# pm25.net
KiCad netlist of a schematic drawn in EAGLE
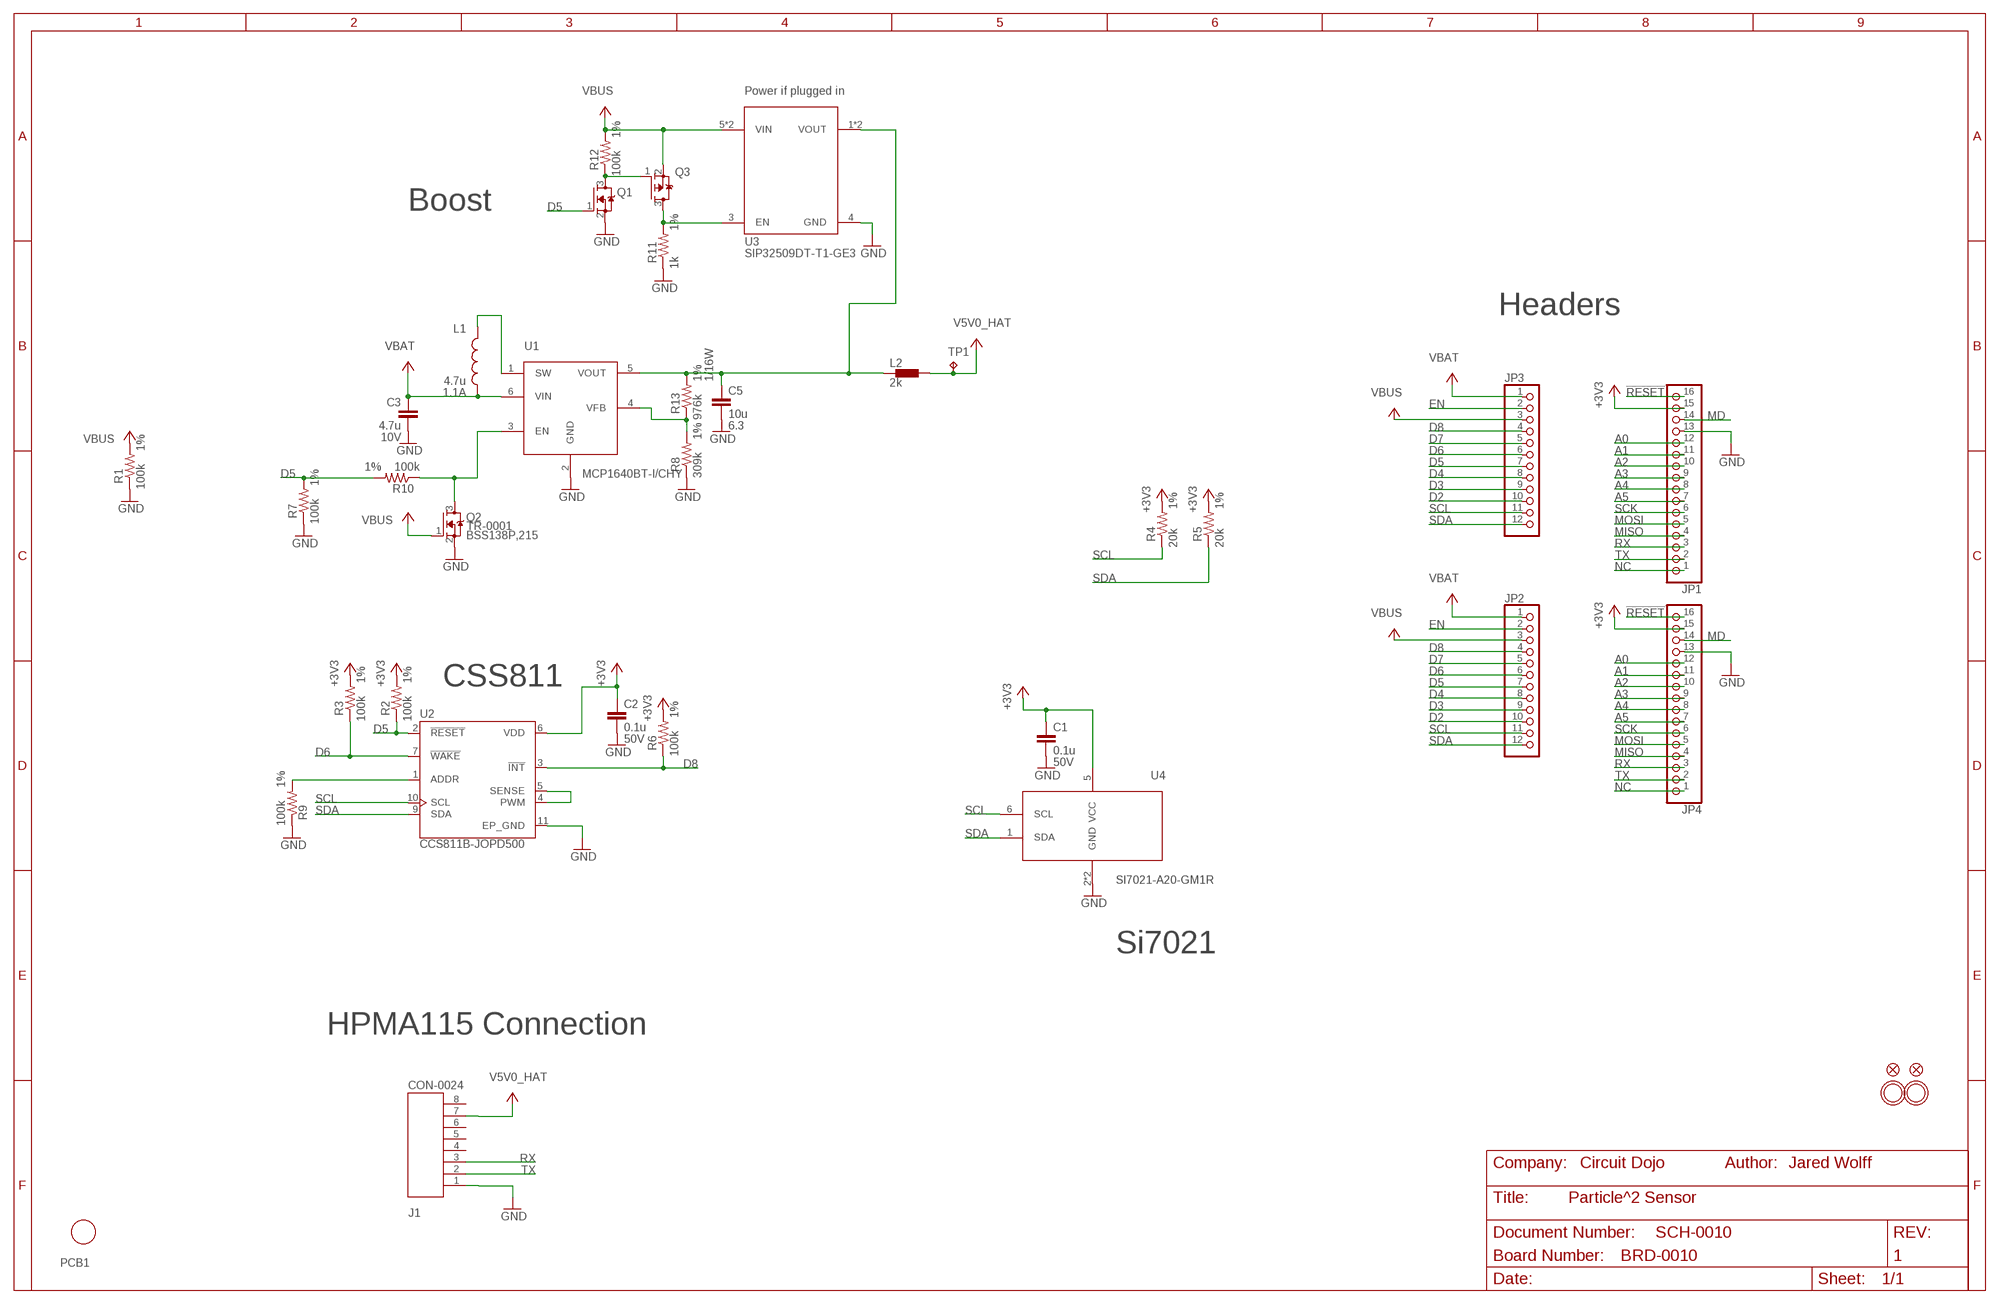
[diagram p0: schematic, sheet 1]

(export (version "E")
  (design (tool "Eeschema 10.0.6"))
  (components
    (comp (ref "C1")
      (value "0.1u")
      (footprint "eagle-import:CAPC1005X55N")
      (fields
        (field (name "VOLTHIGH") "50V")
        (field (name "MF") "Taiyo Yuden")
        (field (name "MPN") "UMK105BJ104KV-F")
      )
      (libsource (lib "eagle-import") (part "CAP-0017"))
    )
    (comp (ref "C2")
      (value "0.1u")
      (footprint "eagle-import:CAPC1005X55N")
      (fields
        (field (name "VOLTHIGH") "50V")
        (field (name "MF") "Taiyo Yuden")
        (field (name "MPN") "UMK105BJ104KV-F")
      )
      (libsource (lib "eagle-import") (part "CAP-0017"))
    )
    (comp (ref "C3")
      (value "4.7u")
      (footprint "eagle-import:C0603")
      (fields (field (name "VOLTHIGH") "10V") (field (name "MPN") "CL10A475MP5LNNC"))
      (libsource (lib "eagle-import") (part "CAP-0010"))
    )
    (comp (ref "C5")
      (value "10u")
      (footprint "eagle-import:C0603")
      (fields (field (name "MPN") "JMK107ABJ106MA-T") (field (name "VOLTHIGH") "6.3"))
      (libsource (lib "eagle-import") (part "CAP-0603-10U-6.3V"))
    )
    (comp (ref "J1")
      (value "CON-0024")
      (footprint "eagle-import:0532610871")
      (fields (field (name "MPN") "0532610871"))
      (libsource (lib "eagle-import") (part "CON-0024"))
    )
    (comp (ref "JP1")
      (value "HEADER-1X16ROUND")
      (footprint "eagle-import:1X16_ROUND")
      (fields (field (name "MPN") "PPPC161LFBN-RC"))
      (libsource (lib "eagle-import") (part "HEADER-1X16ROUND"))
    )
    (comp (ref "JP2")
      (value "HEADER-1X12")
      (footprint "eagle-import:1X12_ROUND")
      (libsource (lib "eagle-import") (part "HEADER-1X12"))
    )
    (comp (ref "JP3")
      (value "HEADER-1X12")
      (footprint "eagle-import:1X12_ROUND")
      (fields (field (name "MPN") "PPPC121LFBN-RC"))
      (libsource (lib "eagle-import") (part "HEADER-1X12"))
    )
    (comp (ref "JP4")
      (value "HEADER-1X16ROUND")
      (footprint "eagle-import:1X16_ROUND")
      (libsource (lib "eagle-import") (part "HEADER-1X16ROUND"))
    )
    (comp (ref "L1")
      (value "4.7u")
      (footprint "eagle-import:IND-2P0X2P0X1P2")
      (fields (field (name "CURRENT") "1.1A") (field (name "MPN") "NRV2012T4R7MGF"))
      (libsource (lib "eagle-import") (part "IND-0003"))
    )
    (comp (ref "L2")
      (value "2k")
      (footprint "eagle-import:R0805")
      (fields (field (name "MPN") "CIM21J202NE"))
      (libsource (lib "eagle-import") (part "FERRITE-0805"))
    )
    (comp (ref "PCB1")
      (value "PCB-PS-CCS811-SI7021")
      (footprint "eagle-import:PLACEHOLDER")
      (fields (field (name "MPN") "BRD-0010"))
      (libsource (lib "eagle-import") (part "PCB-PS-CCS811-SI7021"))
    )
    (comp (ref "Q1")
      (value "TR-0001")
      (footprint "eagle-import:SOT23")
      (fields (field (name "MPN") "BSS138P,215"))
      (libsource (lib "eagle-import") (part "TR-0001"))
    )
    (comp (ref "Q2")
      (value "TR-0001")
      (footprint "eagle-import:SOT23")
      (fields (field (name "MPN") "BSS138P,215"))
      (libsource (lib "eagle-import") (part "TR-0001"))
    )
    (comp (ref "Q3")
      (value "TR-0003")
      (footprint "eagle-import:SOT23")
      (fields (field (name "MPN") "BSS84-7-F"))
      (libsource (lib "eagle-import") (part "TR-0003"))
    )
    (comp (ref "R1")
      (value "100k")
      (footprint "eagle-import:R0402")
      (fields (field (name "TOLERANCE") "1%") (field (name "MPN") "RC0402FR07100KL"))
      (libsource (lib "eagle-import") (part "RES-0041"))
    )
    (comp (ref "R2")
      (value "100k")
      (footprint "eagle-import:R0402")
      (fields (field (name "TOLERANCE") "1%") (field (name "MPN") "RC0402FR07100KL"))
      (libsource (lib "eagle-import") (part "RES-0041"))
    )
    (comp (ref "R3")
      (value "100k")
      (footprint "eagle-import:R0402")
      (fields (field (name "TOLERANCE") "1%") (field (name "MPN") "RC0402FR07100KL"))
      (libsource (lib "eagle-import") (part "RES-0041"))
    )
    (comp (ref "R4")
      (value "20k")
      (footprint "eagle-import:R0402")
      (fields (field (name "TOLERANCE") "1%") (field (name "MPN") "RC0402FR-0720KL"))
      (libsource (lib "eagle-import") (part "RES-0054"))
    )
    (comp (ref "R5")
      (value "20k")
      (footprint "eagle-import:R0402")
      (fields (field (name "TOLERANCE") "1%") (field (name "MPN") "RC0402FR-0720KL"))
      (libsource (lib "eagle-import") (part "RES-0054"))
    )
    (comp (ref "R6")
      (value "100k")
      (footprint "eagle-import:R0402")
      (fields (field (name "TOLERANCE") "1%") (field (name "MPN") "RC0402FR07100KL"))
      (libsource (lib "eagle-import") (part "RES-0041"))
    )
    (comp (ref "R7")
      (value "100k")
      (footprint "eagle-import:R0402")
      (fields (field (name "TOLERANCE") "1%") (field (name "MPN") "RC0402FR07100KL"))
      (libsource (lib "eagle-import") (part "RES-0041"))
    )
    (comp (ref "R8")
      (value "309k")
      (footprint "eagle-import:R0402")
      (fields
        (field (name "MPN") "RC0402FR-07309KL")
        (field (name "POWER") "1/16W")
        (field (name "TOLERANCE") "1%")
      )
      (libsource (lib "eagle-import") (part "RES-0402-309K-1%"))
    )
    (comp (ref "R9")
      (value "100k")
      (footprint "eagle-import:R0402")
      (fields (field (name "TOLERANCE") "1%") (field (name "MPN") "RC0402FR07100KL"))
      (libsource (lib "eagle-import") (part "RES-0041"))
    )
    (comp (ref "R10")
      (value "100k")
      (footprint "eagle-import:R0402")
      (fields (field (name "TOLERANCE") "1%") (field (name "MPN") "RC0402FR07100KL"))
      (libsource (lib "eagle-import") (part "RES-0041"))
    )
    (comp (ref "R11")
      (value "1k")
      (footprint "eagle-import:R0402")
      (fields
        (field (name "MPN") "RCS04021K00FKED")
        (field (name "POWER") "1/5W")
        (field (name "TOLERANCE") "1%")
      )
      (libsource (lib "eagle-import") (part "RES-0402-1K-1%"))
    )
    (comp (ref "R12")
      (value "100k")
      (footprint "eagle-import:R0402")
      (fields (field (name "TOLERANCE") "1%") (field (name "MPN") "RC0402FR07100KL"))
      (libsource (lib "eagle-import") (part "RES-0041"))
    )
    (comp (ref "R13")
      (value "976k")
      (footprint "eagle-import:R0402")
      (fields
        (field (name "MPN") "RC0402FR-07976KL")
        (field (name "POWER") "1/16W")
        (field (name "TOLERANCE") "1%")
      )
      (libsource (lib "eagle-import") (part "RES-0402-976K-1%"))
    )
    (comp (ref "TP1")
      (value "TP")
      (footprint "eagle-import:TP-1P27")
      (libsource (lib "eagle-import") (part "TP"))
    )
    (comp (ref "U$31")
      (value "MOUNTINGHOLE2.5")
      (footprint "eagle-import:MOUNTINGHOLE_2.5_PLATED")
      (libsource (lib "eagle-import") (part "MOUNTINGHOLE2.5"))
    )
    (comp (ref "U$32")
      (value "MOUNTINGHOLE2.5")
      (footprint "eagle-import:MOUNTINGHOLE_2.5_PLATED")
      (libsource (lib "eagle-import") (part "MOUNTINGHOLE2.5"))
    )
    (comp (ref "U$34")
      (value "FIDUCIAL\"\"")
      (footprint "eagle-import:FIDUCIAL_1MM")
      (libsource (lib "eagle-import") (part "FIDUCIAL{dblquote}{dblquote}"))
    )
    (comp (ref "U$35")
      (value "FIDUCIAL\"\"")
      (footprint "eagle-import:FIDUCIAL_1MM")
      (libsource (lib "eagle-import") (part "FIDUCIAL{dblquote}{dblquote}"))
    )
    (comp (ref "U1")
      (value "POWER-VREG-FB-EN-SW-350MA")
      (footprint "eagle-import:SOT23-6")
      (fields (field (name "MPN") "MCP1640BT-I/CHY"))
      (libsource (lib "eagle-import") (part "POWER-VREG-FB-EN-SW-350MA"))
    )
    (comp (ref "U2")
      (value "CCS811B-JOPD500")
      (footprint "eagle-import:SON60P400X270X110-11N")
      (fields (field (name "MF") "ams"))
      (libsource (lib "eagle-import") (part "CCS811B-JOPD500"))
    )
    (comp (ref "U3")
      (value "POWER-SWITCH-SIP32509DT")
      (footprint "eagle-import:SOT23-6")
      (fields (field (name "MPN") "SIP32509DT-T1-GE3"))
      (libsource (lib "eagle-import") (part "POWER-SWITCH-SIP32509DT"))
    )
    (comp (ref "U4")
      (value "SI7021-A20-GM1R")
      (footprint "eagle-import:SON100P300X300X80-7N")
      (fields (field (name "MPN") "SI7021-A20-GM1R"))
      (libsource (lib "eagle-import") (part "SI7021-A20-GM1R"))
    )
  )
  (nets
    (net (code "1") (name "+3V3") (class "Default")
      (node (ref "C1") (pin "1") (pinfunction "1_1") (pintype "passive"))
      (node (ref "C2") (pin "1") (pinfunction "1_1") (pintype "passive"))
      (node (ref "JP1") (pin "15") (pinfunction "15_15") (pintype "passive"))
      (node (ref "JP4") (pin "15") (pinfunction "15_15") (pintype "passive"))
      (node (ref "R2") (pin "2") (pinfunction "2_2") (pintype "passive"))
      (node (ref "R3") (pin "2") (pinfunction "2_2") (pintype "passive"))
      (node (ref "R4") (pin "2") (pinfunction "2_2") (pintype "passive"))
      (node (ref "R5") (pin "2") (pinfunction "2_2") (pintype "passive"))
      (node (ref "R6") (pin "2") (pinfunction "2_2") (pintype "passive"))
      (node (ref "U2") (pin "6") (pinfunction "VDD_6") (pintype "power_in"))
      (node (ref "U4") (pin "5") (pinfunction "VCC_5") (pintype "bidirectional"))
    )
    (net (code "2") (name "/A0") (class "Default")
      (node (ref "JP1") (pin "12") (pinfunction "12_12") (pintype "passive"))
      (node (ref "JP4") (pin "12") (pinfunction "12_12") (pintype "passive"))
    )
    (net (code "3") (name "/A1") (class "Default")
      (node (ref "JP1") (pin "11") (pinfunction "11_11") (pintype "passive"))
      (node (ref "JP4") (pin "11") (pinfunction "11_11") (pintype "passive"))
    )
    (net (code "4") (name "/A2") (class "Default")
      (node (ref "JP1") (pin "10") (pinfunction "10_10") (pintype "passive"))
      (node (ref "JP4") (pin "10") (pinfunction "10_10") (pintype "passive"))
    )
    (net (code "5") (name "/A3") (class "Default")
      (node (ref "JP1") (pin "9") (pinfunction "9_9") (pintype "passive"))
      (node (ref "JP4") (pin "9") (pinfunction "9_9") (pintype "passive"))
    )
    (net (code "6") (name "/A4") (class "Default")
      (node (ref "JP1") (pin "8") (pinfunction "8_8") (pintype "passive"))
      (node (ref "JP4") (pin "8") (pinfunction "8_8") (pintype "passive"))
    )
    (net (code "7") (name "/A5") (class "Default")
      (node (ref "JP1") (pin "7") (pinfunction "7_7") (pintype "passive"))
      (node (ref "JP4") (pin "7") (pinfunction "7_7") (pintype "passive"))
    )
    (net (code "8") (name "/D2") (class "Default")
      (node (ref "JP2") (pin "10") (pinfunction "10_10") (pintype "passive"))
      (node (ref "JP3") (pin "10") (pinfunction "10_10") (pintype "passive"))
    )
    (net (code "9") (name "/D3") (class "Default")
      (node (ref "JP2") (pin "9") (pinfunction "9_9") (pintype "passive"))
      (node (ref "JP3") (pin "9") (pinfunction "9_9") (pintype "passive"))
    )
    (net (code "10") (name "/D4") (class "Default")
      (node (ref "JP2") (pin "8") (pinfunction "8_8") (pintype "passive"))
      (node (ref "JP3") (pin "8") (pinfunction "8_8") (pintype "passive"))
    )
    (net (code "11") (name "/D5") (class "Default")
      (node (ref "JP2") (pin "7") (pinfunction "7_7") (pintype "passive"))
      (node (ref "JP3") (pin "7") (pinfunction "7_7") (pintype "passive"))
      (node (ref "Q1") (pin "1") (pinfunction "G_1") (pintype "bidirectional"))
      (node (ref "R10") (pin "2") (pinfunction "2_2") (pintype "passive"))
      (node (ref "R2") (pin "1") (pinfunction "1_1") (pintype "passive"))
      (node (ref "R7") (pin "2") (pinfunction "2_2") (pintype "passive"))
      (node (ref "U2") (pin "2") (pinfunction "~{RESET}_2") (pintype "input"))
    )
    (net (code "12") (name "/D6") (class "Default")
      (node (ref "JP2") (pin "6") (pinfunction "6_6") (pintype "passive"))
      (node (ref "JP3") (pin "6") (pinfunction "6_6") (pintype "passive"))
      (node (ref "R3") (pin "1") (pinfunction "1_1") (pintype "passive"))
      (node (ref "U2") (pin "7") (pinfunction "~{WAKE}_7") (pintype "input"))
    )
    (net (code "13") (name "/D7") (class "Default")
      (node (ref "JP2") (pin "5") (pinfunction "5_5") (pintype "passive"))
      (node (ref "JP3") (pin "5") (pinfunction "5_5") (pintype "passive"))
    )
    (net (code "14") (name "/D8") (class "Default")
      (node (ref "JP2") (pin "4") (pinfunction "4_4") (pintype "passive"))
      (node (ref "JP3") (pin "4") (pinfunction "4_4") (pintype "passive"))
      (node (ref "R6") (pin "1") (pinfunction "1_1") (pintype "passive"))
      (node (ref "U2") (pin "3") (pinfunction "~{INT}_3") (pintype "output"))
    )
    (net (code "15") (name "/EN") (class "Default")
      (node (ref "JP2") (pin "2") (pinfunction "2_2") (pintype "passive"))
      (node (ref "JP3") (pin "2") (pinfunction "2_2") (pintype "passive"))
    )
    (net (code "16") (name "/MD") (class "Default")
      (node (ref "JP1") (pin "14") (pinfunction "14_14") (pintype "passive"))
      (node (ref "JP4") (pin "14") (pinfunction "14_14") (pintype "passive"))
    )
    (net (code "17") (name "/MISO") (class "Default")
      (node (ref "JP1") (pin "4") (pinfunction "4_4") (pintype "passive"))
      (node (ref "JP4") (pin "4") (pinfunction "4_4") (pintype "passive"))
    )
    (net (code "18") (name "/MOSI") (class "Default")
      (node (ref "JP1") (pin "5") (pinfunction "5_5") (pintype "passive"))
      (node (ref "JP4") (pin "5") (pinfunction "5_5") (pintype "passive"))
    )
    (net (code "19") (name "/NC") (class "Default")
      (node (ref "JP1") (pin "1") (pinfunction "1_1") (pintype "passive"))
      (node (ref "JP4") (pin "1") (pinfunction "1_1") (pintype "passive"))
    )
    (net (code "20") (name "/RX") (class "Default")
      (node (ref "J1") (pin "3") (pinfunction "P$3_3") (pintype "bidirectional"))
      (node (ref "JP1") (pin "3") (pinfunction "3_3") (pintype "passive"))
      (node (ref "JP4") (pin "3") (pinfunction "3_3") (pintype "passive"))
    )
    (net (code "21") (name "/SCK") (class "Default")
      (node (ref "JP1") (pin "6") (pinfunction "6_6") (pintype "passive"))
      (node (ref "JP4") (pin "6") (pinfunction "6_6") (pintype "passive"))
    )
    (net (code "22") (name "/SCL") (class "Default")
      (node (ref "JP2") (pin "11") (pinfunction "11_11") (pintype "passive"))
      (node (ref "JP3") (pin "11") (pinfunction "11_11") (pintype "passive"))
      (node (ref "R4") (pin "1") (pinfunction "1_1") (pintype "passive"))
      (node (ref "U2") (pin "10") (pinfunction "SCL_10") (pintype "input"))
      (node (ref "U4") (pin "6") (pinfunction "SCL_6") (pintype "bidirectional"))
    )
    (net (code "23") (name "/SDA") (class "Default")
      (node (ref "JP2") (pin "12") (pinfunction "12_12") (pintype "passive"))
      (node (ref "JP3") (pin "12") (pinfunction "12_12") (pintype "passive"))
      (node (ref "R5") (pin "1") (pinfunction "1_1") (pintype "passive"))
      (node (ref "U2") (pin "9") (pinfunction "SDA_9") (pintype "bidirectional"))
      (node (ref "U4") (pin "1") (pinfunction "SDA_1") (pintype "bidirectional"))
    )
    (net (code "24") (name "/TX") (class "Default")
      (node (ref "J1") (pin "2") (pinfunction "P$2_2") (pintype "bidirectional"))
      (node (ref "JP1") (pin "2") (pinfunction "2_2") (pintype "passive"))
      (node (ref "JP4") (pin "2") (pinfunction "2_2") (pintype "passive"))
    )
    (net (code "25") (name "/~{RESET}") (class "Default")
      (node (ref "JP1") (pin "16") (pinfunction "16_16") (pintype "passive"))
      (node (ref "JP4") (pin "16") (pinfunction "16_16") (pintype "passive"))
    )
    (net (code "26") (name "GND") (class "Default")
      (node (ref "C1") (pin "2") (pinfunction "2_2") (pintype "passive"))
      (node (ref "C2") (pin "2") (pinfunction "2_2") (pintype "passive"))
      (node (ref "C3") (pin "2") (pinfunction "2_2") (pintype "passive"))
      (node (ref "C5") (pin "2") (pinfunction "2_2") (pintype "passive"))
      (node (ref "J1") (pin "1") (pinfunction "P$1_1") (pintype "bidirectional"))
      (node (ref "JP1") (pin "13") (pinfunction "13_13") (pintype "passive"))
      (node (ref "JP4") (pin "13") (pinfunction "13_13") (pintype "passive"))
      (node (ref "Q1") (pin "2") (pinfunction "S_2") (pintype "bidirectional"))
      (node (ref "Q2") (pin "2") (pinfunction "S_2") (pintype "bidirectional"))
      (node (ref "R1") (pin "1") (pinfunction "1_1") (pintype "passive"))
      (node (ref "R11") (pin "1") (pinfunction "1_1") (pintype "passive"))
      (node (ref "R7") (pin "1") (pinfunction "1_1") (pintype "passive"))
      (node (ref "R8") (pin "1") (pinfunction "1_1") (pintype "passive"))
      (node (ref "R9") (pin "1") (pinfunction "1_1") (pintype "passive"))
      (node (ref "U1") (pin "2") (pinfunction "GND_2") (pintype "bidirectional"))
      (node (ref "U2") (pin "11") (pinfunction "EP_GND_11") (pintype "power_in"))
      (node (ref "U3") (pin "4") (pinfunction "GND_4") (pintype "power_in"))
      (node (ref "U4") (pin "2") (pinfunction "GND_2") (pintype "bidirectional"))
      (node (ref "U4") (pin "7") (pinfunction "GND_7") (pintype "bidirectional"))
    )
    (net (code "27") (name "Net-(L1-1)") (class "Default")
      (node (ref "L1") (pin "P$1") (pinfunction "1_P$1") (pintype "passive"))
      (node (ref "U1") (pin "1") (pinfunction "SW_1") (pintype "bidirectional"))
    )
    (net (code "28") (name "Net-(Q1-D)") (class "Default")
      (node (ref "Q1") (pin "3") (pinfunction "D_3") (pintype "bidirectional"))
      (node (ref "Q3") (pin "1") (pinfunction "G_1") (pintype "passive"))
      (node (ref "R12") (pin "1") (pinfunction "1_1") (pintype "passive"))
    )
    (net (code "29") (name "Net-(Q2-D)") (class "Default")
      (node (ref "Q2") (pin "3") (pinfunction "D_3") (pintype "bidirectional"))
      (node (ref "R10") (pin "1") (pinfunction "1_1") (pintype "passive"))
      (node (ref "U1") (pin "3") (pinfunction "EN_3") (pintype "bidirectional"))
    )
    (net (code "30") (name "Net-(Q3-D)") (class "Default")
      (node (ref "Q3") (pin "3") (pinfunction "D_3") (pintype "passive"))
      (node (ref "R11") (pin "2") (pinfunction "2_2") (pintype "passive"))
      (node (ref "U3") (pin "3") (pinfunction "EN_3") (pintype "input"))
    )
    (net (code "31") (name "Net-(U1-VFB)") (class "Default")
      (node (ref "R13") (pin "1") (pinfunction "1_1") (pintype "passive"))
      (node (ref "R8") (pin "2") (pinfunction "2_2") (pintype "passive"))
      (node (ref "U1") (pin "4") (pinfunction "VFB_4") (pintype "bidirectional"))
    )
    (net (code "32") (name "Net-(U1-VOUT)") (class "Default")
      (node (ref "C5") (pin "1") (pinfunction "1_1") (pintype "passive"))
      (node (ref "L2") (pin "1") (pinfunction "1_1") (pintype "passive"))
      (node (ref "R13") (pin "2") (pinfunction "2_2") (pintype "passive"))
      (node (ref "U1") (pin "5") (pinfunction "VOUT_5") (pintype "bidirectional"))
      (node (ref "U3") (pin "1") (pinfunction "VOUT_1") (pintype "power_in"))
      (node (ref "U3") (pin "2") (pinfunction "VOUT_2") (pintype "power_in"))
    )
    (net (code "33") (name "Net-(U2-ADDR)") (class "Default")
      (node (ref "R9") (pin "2") (pinfunction "2_2") (pintype "passive"))
      (node (ref "U2") (pin "1") (pinfunction "ADDR_1") (pintype "input"))
    )
    (net (code "34") (name "Net-(U2-PWM)") (class "Default")
      (node (ref "U2") (pin "4") (pinfunction "PWM_4") (pintype "output"))
      (node (ref "U2") (pin "5") (pinfunction "SENSE_5") (pintype "output"))
    )
    (net (code "35") (name "V5V0_HAT") (class "Default")
      (node (ref "J1") (pin "7") (pinfunction "P$7_7") (pintype "bidirectional"))
      (node (ref "L2") (pin "2") (pinfunction "2_2") (pintype "passive"))
      (node (ref "TP1") (pin "P$1") (pinfunction "TP_P$1") (pintype "input"))
      (node (ref "TP1") (pin "P$2") (pinfunction "TP_P$2") (pintype "input"))
      (node (ref "TP1") (pin "TP") (pinfunction "TP_TP") (pintype "input"))
    )
    (net (code "36") (name "VBAT") (class "Default")
      (node (ref "C3") (pin "1") (pinfunction "1_1") (pintype "passive"))
      (node (ref "JP2") (pin "1") (pinfunction "1_1") (pintype "passive"))
      (node (ref "JP3") (pin "1") (pinfunction "1_1") (pintype "passive"))
      (node (ref "L1") (pin "P$2") (pinfunction "2_P$2") (pintype "passive"))
      (node (ref "U1") (pin "6") (pinfunction "VIN_6") (pintype "bidirectional"))
    )
    (net (code "37") (name "VBUS") (class "Default")
      (node (ref "JP2") (pin "3") (pinfunction "3_3") (pintype "passive"))
      (node (ref "JP3") (pin "3") (pinfunction "3_3") (pintype "passive"))
      (node (ref "Q2") (pin "1") (pinfunction "G_1") (pintype "bidirectional"))
      (node (ref "Q3") (pin "2") (pinfunction "S_2") (pintype "passive"))
      (node (ref "R1") (pin "2") (pinfunction "2_2") (pintype "passive"))
      (node (ref "R12") (pin "2") (pinfunction "2_2") (pintype "passive"))
      (node (ref "U3") (pin "5") (pinfunction "VIN_5") (pintype "power_in"))
      (node (ref "U3") (pin "6") (pinfunction "VIN_6") (pintype "power_in"))
    )
    (net (code "38") (name "unconnected-(J1-P$4-Pad4)") (class "Default")
      (node (ref "J1") (pin "4") (pinfunction "P$4_4") (pintype "bidirectional"))
    )
    (net (code "39") (name "unconnected-(J1-P$5-Pad5)") (class "Default")
      (node (ref "J1") (pin "5") (pinfunction "P$5_5") (pintype "bidirectional"))
    )
    (net (code "40") (name "unconnected-(J1-P$6-Pad6)") (class "Default")
      (node (ref "J1") (pin "6") (pinfunction "P$6_6") (pintype "bidirectional"))
    )
    (net (code "41") (name "unconnected-(J1-P$8-Pad8)") (class "Default")
      (node (ref "J1") (pin "8") (pinfunction "P$8_8") (pintype "bidirectional"))
    )
  )
)
